# ZeroGecko110BreakoutV1.net
KiCad netlist of a schematic drawn in EAGLE
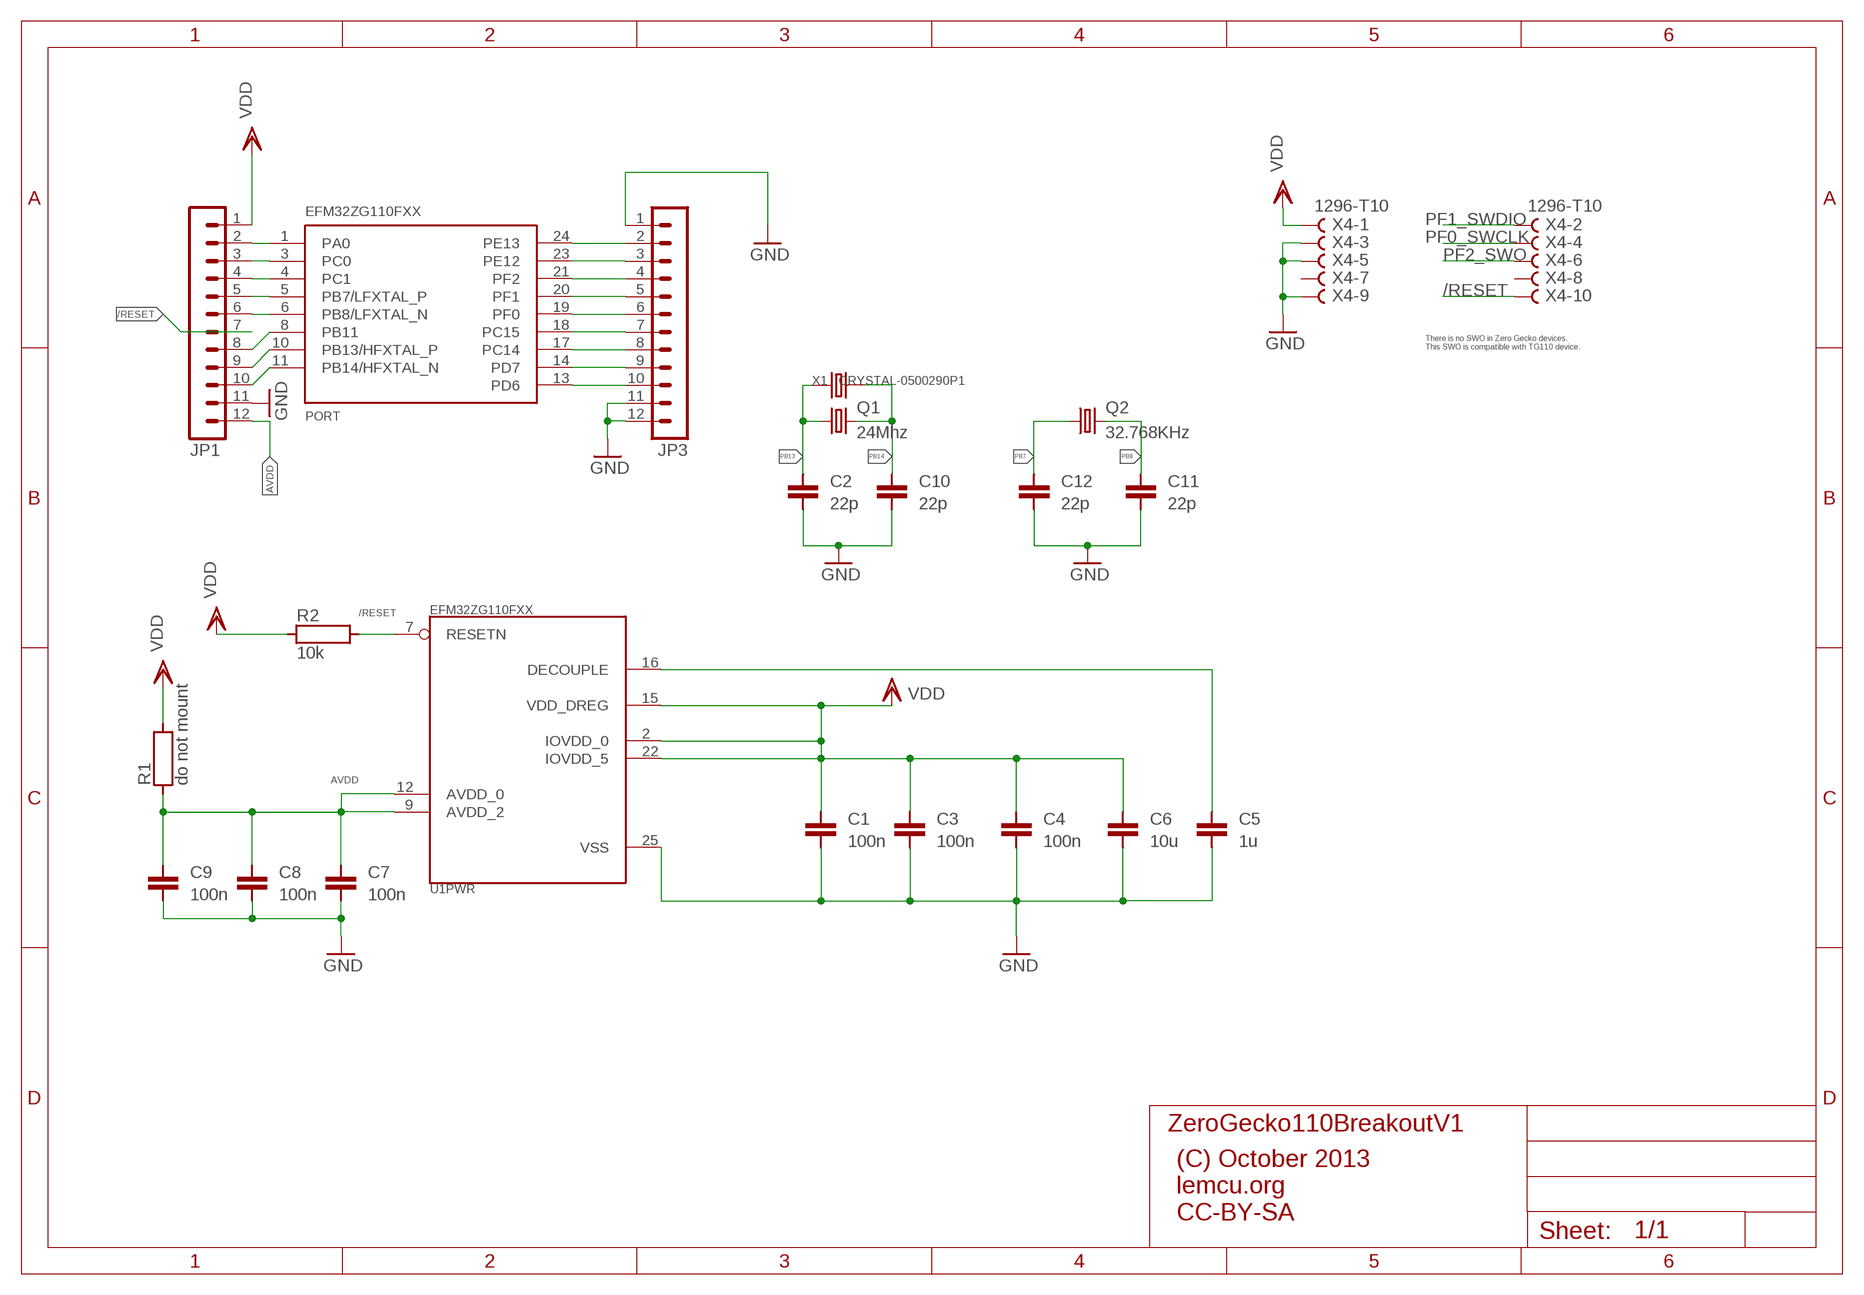
[diagram p0: schematic, sheet 1]

(export (version "E")
  (design (tool "Eeschema 10.0.6"))
  (components
    (comp (ref "C1")
      (value "100n")
      (footprint "eagle-import:C0603")
      (libsource (lib "eagle-import") (part "C0603"))
    )
    (comp (ref "C2")
      (value "22p")
      (footprint "eagle-import:C0603")
      (libsource (lib "eagle-import") (part "C0603"))
    )
    (comp (ref "C3")
      (value "100n")
      (footprint "eagle-import:C0603")
      (libsource (lib "eagle-import") (part "C0603"))
    )
    (comp (ref "C4")
      (value "100n")
      (footprint "eagle-import:C0603")
      (libsource (lib "eagle-import") (part "C0603"))
    )
    (comp (ref "C5")
      (value "1u")
      (footprint "eagle-import:C0805")
      (libsource (lib "eagle-import") (part "C0805"))
    )
    (comp (ref "C6")
      (value "10u")
      (footprint "eagle-import:C0805")
      (libsource (lib "eagle-import") (part "C0805"))
    )
    (comp (ref "C7")
      (value "100n")
      (footprint "eagle-import:C0603")
      (libsource (lib "eagle-import") (part "C0603"))
    )
    (comp (ref "C8")
      (value "100n")
      (footprint "eagle-import:C0603")
      (libsource (lib "eagle-import") (part "C0603"))
    )
    (comp (ref "C9")
      (value "100n")
      (footprint "eagle-import:C0603")
      (libsource (lib "eagle-import") (part "C0603"))
    )
    (comp (ref "C10")
      (value "22p")
      (footprint "eagle-import:C0603")
      (libsource (lib "eagle-import") (part "C0603"))
    )
    (comp (ref "C11")
      (value "22p")
      (footprint "eagle-import:C0603")
      (libsource (lib "eagle-import") (part "C0603"))
    )
    (comp (ref "C12")
      (value "22p")
      (footprint "eagle-import:C0603")
      (libsource (lib "eagle-import") (part "C0603"))
    )
    (comp (ref "JP1")
      (value "MA12-1")
      (footprint "eagle-import:MA12-1")
      (libsource (lib "eagle-import") (part "MA12-1"))
    )
    (comp (ref "JP3")
      (value "MA12-1")
      (footprint "eagle-import:MA12-1")
      (libsource (lib "eagle-import") (part "MA12-1"))
    )
    (comp (ref "Q1")
      (value "24Mhz")
      (footprint "eagle-import:HC49U-V")
      (libsource (lib "eagle-import") (part "CRYSTALHC49U-V"))
    )
    (comp (ref "Q2")
      (value "32.768KHz")
      (footprint "eagle-import:TC26V")
      (libsource (lib "eagle-import") (part "CRYSTALTC26V"))
    )
    (comp (ref "R1")
      (value "do not mount")
      (footprint "eagle-import:R0805")
      (libsource (lib "eagle-import") (part "R0805"))
    )
    (comp (ref "R2")
      (value "10k")
      (footprint "eagle-import:R0603")
      (libsource (lib "eagle-import") (part "R0603"))
    )
    (comp (ref "U1")
      (value "EFM32ZG110FXX")
      (footprint "eagle-import:QFN24")
      (libsource (lib "eagle-import") (part "EFM32ZG110FXX"))
    )
    (comp (ref "X1")
      (value "CRYSTAL-0500290P1")
      (footprint "eagle-import:2P-SMD-5.0X3.2")
      (libsource (lib "eagle-import") (part "CRYSTAL-0500290P1"))
    )
    (comp (ref "X4")
      (value "1296-T10")
      (footprint "eagle-import:1296-10")
      (libsource (lib "eagle-import") (part "1296-T10"))
    )
  )
  (nets
    (net (code "1") (name "/PF0_SWCLK") (class "Default")
      (node (ref "JP3") (pin "6") (pinfunction "6_6") (pintype "passive"))
      (node (ref "U1") (pin "19") (pinfunction "PF0_19") (pintype "bidirectional"))
      (node (ref "X4") (pin "4") (pinfunction "B_4") (pintype "passive"))
    )
    (net (code "2") (name "/PF1_SWDIO") (class "Default")
      (node (ref "JP3") (pin "5") (pinfunction "5_5") (pintype "passive"))
      (node (ref "U1") (pin "20") (pinfunction "PF1_20") (pintype "bidirectional"))
      (node (ref "X4") (pin "2") (pinfunction "B_2") (pintype "passive"))
    )
    (net (code "3") (name "/PF2_SWO") (class "Default")
      (node (ref "JP3") (pin "4") (pinfunction "4_4") (pintype "passive"))
      (node (ref "U1") (pin "21") (pinfunction "PF2_21") (pintype "bidirectional"))
      (node (ref "X4") (pin "6") (pinfunction "B_6") (pintype "passive"))
    )
    (net (code "4") (name "AVDD") (class "Default")
      (node (ref "C7") (pin "2") (pinfunction "2_2") (pintype "passive"))
      (node (ref "C8") (pin "2") (pinfunction "2_2") (pintype "passive"))
      (node (ref "C9") (pin "2") (pinfunction "2_2") (pintype "passive"))
      (node (ref "JP1") (pin "12") (pinfunction "12_12") (pintype "passive"))
      (node (ref "R1") (pin "1") (pinfunction "1_1") (pintype "passive"))
      (node (ref "U1") (pin "12") (pinfunction "AVDD_0_12") (pintype "power_in"))
      (node (ref "U1") (pin "9") (pinfunction "AVDD_2_9") (pintype "power_in"))
    )
    (net (code "5") (name "GND") (class "Default")
      (node (ref "C1") (pin "1") (pinfunction "1_1") (pintype "passive"))
      (node (ref "C10") (pin "1") (pinfunction "1_1") (pintype "passive"))
      (node (ref "C11") (pin "1") (pinfunction "1_1") (pintype "passive"))
      (node (ref "C12") (pin "1") (pinfunction "1_1") (pintype "passive"))
      (node (ref "C2") (pin "1") (pinfunction "1_1") (pintype "passive"))
      (node (ref "C3") (pin "1") (pinfunction "1_1") (pintype "passive"))
      (node (ref "C4") (pin "1") (pinfunction "1_1") (pintype "passive"))
      (node (ref "C5") (pin "1") (pinfunction "1_1") (pintype "passive"))
      (node (ref "C6") (pin "1") (pinfunction "1_1") (pintype "passive"))
      (node (ref "C7") (pin "1") (pinfunction "1_1") (pintype "passive"))
      (node (ref "C8") (pin "1") (pinfunction "1_1") (pintype "passive"))
      (node (ref "C9") (pin "1") (pinfunction "1_1") (pintype "passive"))
      (node (ref "JP1") (pin "11") (pinfunction "11_11") (pintype "passive"))
      (node (ref "JP3") (pin "1") (pinfunction "1_1") (pintype "passive"))
      (node (ref "JP3") (pin "11") (pinfunction "11_11") (pintype "passive"))
      (node (ref "JP3") (pin "12") (pinfunction "12_12") (pintype "passive"))
      (node (ref "U1") (pin "25") (pinfunction "VSS_25") (pintype "power_in"))
      (node (ref "X4") (pin "3") (pinfunction "B_3") (pintype "passive"))
      (node (ref "X4") (pin "5") (pinfunction "B_5") (pintype "passive"))
      (node (ref "X4") (pin "9") (pinfunction "B_9") (pintype "passive"))
    )
    (net (code "6") (name "Net-(U1A-PA0)") (class "Default")
      (node (ref "JP1") (pin "2") (pinfunction "2_2") (pintype "passive"))
      (node (ref "U1") (pin "1") (pinfunction "PA0_1") (pintype "bidirectional"))
    )
    (net (code "7") (name "Net-(U1A-PB11)") (class "Default")
      (node (ref "JP1") (pin "8") (pinfunction "8_8") (pintype "passive"))
      (node (ref "U1") (pin "8") (pinfunction "PB11_8") (pintype "bidirectional"))
    )
    (net (code "8") (name "Net-(U1A-PC0)") (class "Default")
      (node (ref "JP1") (pin "3") (pinfunction "3_3") (pintype "passive"))
      (node (ref "U1") (pin "3") (pinfunction "PC0_3") (pintype "bidirectional"))
    )
    (net (code "9") (name "Net-(U1A-PC1)") (class "Default")
      (node (ref "JP1") (pin "4") (pinfunction "4_4") (pintype "passive"))
      (node (ref "U1") (pin "4") (pinfunction "PC1_4") (pintype "bidirectional"))
    )
    (net (code "10") (name "Net-(U1A-PC14)") (class "Default")
      (node (ref "JP3") (pin "8") (pinfunction "8_8") (pintype "passive"))
      (node (ref "U1") (pin "17") (pinfunction "PC14_17") (pintype "bidirectional"))
    )
    (net (code "11") (name "Net-(U1A-PC15)") (class "Default")
      (node (ref "JP3") (pin "7") (pinfunction "7_7") (pintype "passive"))
      (node (ref "U1") (pin "18") (pinfunction "PC15_18") (pintype "bidirectional"))
    )
    (net (code "12") (name "Net-(U1A-PD6)") (class "Default")
      (node (ref "JP3") (pin "10") (pinfunction "10_10") (pintype "passive"))
      (node (ref "U1") (pin "13") (pinfunction "PD6_13") (pintype "bidirectional"))
    )
    (net (code "13") (name "Net-(U1A-PD7)") (class "Default")
      (node (ref "JP3") (pin "9") (pinfunction "9_9") (pintype "passive"))
      (node (ref "U1") (pin "14") (pinfunction "PD7_14") (pintype "bidirectional"))
    )
    (net (code "14") (name "Net-(U1A-PE12)") (class "Default")
      (node (ref "JP3") (pin "3") (pinfunction "3_3") (pintype "passive"))
      (node (ref "U1") (pin "23") (pinfunction "PE12_23") (pintype "bidirectional"))
    )
    (net (code "15") (name "Net-(U1A-PE13)") (class "Default")
      (node (ref "JP3") (pin "2") (pinfunction "2_2") (pintype "passive"))
      (node (ref "U1") (pin "24") (pinfunction "PE13_24") (pintype "bidirectional"))
    )
    (net (code "16") (name "Net-(U1B-DECOUPLE)") (class "Default")
      (node (ref "C5") (pin "2") (pinfunction "2_2") (pintype "passive"))
      (node (ref "U1") (pin "16") (pinfunction "DECOUPLE_16") (pintype "power_in"))
    )
    (net (code "17") (name "PB7") (class "Default")
      (node (ref "C12") (pin "2") (pinfunction "2_2") (pintype "passive"))
      (node (ref "JP1") (pin "5") (pinfunction "5_5") (pintype "passive"))
      (node (ref "Q2") (pin "1") (pinfunction "1_1") (pintype "passive"))
      (node (ref "U1") (pin "5") (pinfunction "PB7/LFXTAL_P_5") (pintype "bidirectional"))
    )
    (net (code "18") (name "PB8") (class "Default")
      (node (ref "C11") (pin "2") (pinfunction "2_2") (pintype "passive"))
      (node (ref "JP1") (pin "6") (pinfunction "6_6") (pintype "passive"))
      (node (ref "Q2") (pin "2") (pinfunction "2_2") (pintype "passive"))
      (node (ref "U1") (pin "6") (pinfunction "PB8/LFXTAL_N_6") (pintype "bidirectional"))
    )
    (net (code "19") (name "PB13") (class "Default")
      (node (ref "C2") (pin "2") (pinfunction "2_2") (pintype "passive"))
      (node (ref "JP1") (pin "9") (pinfunction "9_9") (pintype "passive"))
      (node (ref "Q1") (pin "1") (pinfunction "1_1") (pintype "passive"))
      (node (ref "U1") (pin "10") (pinfunction "PB13/HFXTAL_P_10") (pintype "bidirectional"))
      (node (ref "X1") (pin "1") (pinfunction "1_1") (pintype "passive"))
    )
    (net (code "20") (name "PB14") (class "Default")
      (node (ref "C10") (pin "2") (pinfunction "2_2") (pintype "passive"))
      (node (ref "JP1") (pin "10") (pinfunction "10_10") (pintype "passive"))
      (node (ref "Q1") (pin "2") (pinfunction "2_2") (pintype "passive"))
      (node (ref "U1") (pin "11") (pinfunction "PB14/HFXTAL_N_11") (pintype "bidirectional"))
      (node (ref "X1") (pin "2") (pinfunction "2_2") (pintype "passive"))
    )
    (net (code "21") (name "VDD") (class "Default")
      (node (ref "C1") (pin "2") (pinfunction "2_2") (pintype "passive"))
      (node (ref "C3") (pin "2") (pinfunction "2_2") (pintype "passive"))
      (node (ref "C4") (pin "2") (pinfunction "2_2") (pintype "passive"))
      (node (ref "C6") (pin "2") (pinfunction "2_2") (pintype "passive"))
      (node (ref "JP1") (pin "1") (pinfunction "1_1") (pintype "passive"))
      (node (ref "R1") (pin "2") (pinfunction "2_2") (pintype "passive"))
      (node (ref "R2") (pin "1") (pinfunction "1_1") (pintype "passive"))
      (node (ref "U1") (pin "15") (pinfunction "VDD_DREG_15") (pintype "power_in"))
      (node (ref "U1") (pin "2") (pinfunction "IOVDD_0_2") (pintype "power_in"))
      (node (ref "U1") (pin "22") (pinfunction "IOVDD_5_22") (pintype "power_in"))
      (node (ref "X4") (pin "1") (pinfunction "B_1") (pintype "passive"))
    )
    (net (code "22") (name "unconnected-(X4H-B-Pad7)") (class "Default")
      (node (ref "X4") (pin "7") (pinfunction "B_7") (pintype "passive"))
    )
    (net (code "23") (name "unconnected-(X4I-B-Pad8)") (class "Default")
      (node (ref "X4") (pin "8") (pinfunction "B_8") (pintype "passive"))
    )
    (net (code "24") (name "{slash}RESET") (class "Default")
      (node (ref "JP1") (pin "7") (pinfunction "7_7") (pintype "passive"))
      (node (ref "R2") (pin "2") (pinfunction "2_2") (pintype "passive"))
      (node (ref "U1") (pin "7") (pinfunction "RESETN_7") (pintype "passive"))
      (node (ref "X4") (pin "10") (pinfunction "B_10") (pintype "passive"))
    )
  )
)
